# design.net
KiCad netlist of a schematic drawn in Altium Designer
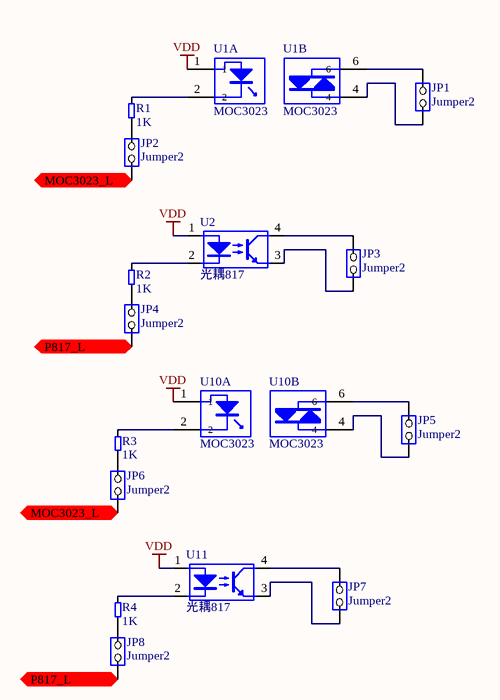
[diagram p0: 光耦隔离.SchDoc]

(export (version "E")
  (design (tool "Eeschema 10.0.6"))
  (components
    (comp (ref "JP1")
      (value "Jumper2")
      (footprint "CON2-P2.54")
      (libsource (lib "Miscellaneous Connectors") (part "Jumper2"))
    )
    (comp (ref "JP2")
      (value "Jumper2")
      (footprint "CON2-P2.54")
      (libsource (lib "Miscellaneous Connectors") (part "Jumper2"))
    )
    (comp (ref "JP3")
      (value "Jumper2")
      (footprint "CON2-P2.54")
      (libsource (lib "Miscellaneous Connectors") (part "Jumper2"))
    )
    (comp (ref "JP4")
      (value "Jumper2")
      (footprint "CON2-P2.54")
      (libsource (lib "Miscellaneous Connectors") (part "Jumper2"))
    )
    (comp (ref "JP5")
      (value "Jumper2")
      (footprint "CON2-P2.54")
      (libsource (lib "Miscellaneous Connectors") (part "Jumper2"))
    )
    (comp (ref "JP6")
      (value "Jumper2")
      (footprint "CON2-P2.54")
      (libsource (lib "Miscellaneous Connectors") (part "Jumper2"))
    )
    (comp (ref "JP7")
      (value "Jumper2")
      (footprint "CON2-P2.54")
      (libsource (lib "Miscellaneous Connectors") (part "Jumper2"))
    )
    (comp (ref "JP8")
      (value "Jumper2")
      (footprint "CON2-P2.54")
      (libsource (lib "Miscellaneous Connectors") (part "Jumper2"))
    )
    (comp (ref "R1")
      (value "1K")
      (footprint "0603")
      (description "电阻")
      (fields (field (name "PUBLISHER") "Altium Limited"))
      (libsource (lib "Miscellaneous Devices") (part "Res1"))
    )
    (comp (ref "R2")
      (value "1K")
      (footprint "0603")
      (description "电阻")
      (fields (field (name "PUBLISHER") "Altium Limited"))
      (libsource (lib "Miscellaneous Devices") (part "Res1"))
    )
    (comp (ref "R3")
      (value "1K")
      (footprint "0603")
      (description "电阻")
      (fields (field (name "PUBLISHER") "Altium Limited"))
      (libsource (lib "Miscellaneous Devices") (part "Res1"))
    )
    (comp (ref "R4")
      (value "1K")
      (footprint "0603")
      (description "电阻")
      (fields (field (name "PUBLISHER") "Altium Limited"))
      (libsource (lib "Miscellaneous Devices") (part "Res1"))
    )
    (comp (ref "U1")
      (value "MOC3023")
      (footprint "SOP-6")
      (description "光耦")
      (fields (field (name "PUBLISHER") "Altium Limited"))
      (libsource (lib "Miscellaneous Devices") (part "MOC3023"))
    )
    (comp (ref "U2")
      (value "光耦817")
      (footprint "LC-SMD-4")
      (libsource (lib "Miscellaneous Devices") (part "光耦817"))
    )
    (comp (ref "U10")
      (value "MOC3023")
      (footprint "SOP-6")
      (description "光耦")
      (fields (field (name "PUBLISHER") "Altium Limited"))
      (libsource (lib "Miscellaneous Devices") (part "MOC3023"))
    )
    (comp (ref "U11")
      (value "光耦817")
      (footprint "LC-SMD-4")
      (libsource (lib "Miscellaneous Devices") (part "光耦817"))
    )
  )
  (nets
    (net (code "1") (name "/MOC3023_L") (class "Default")
      (node (ref "JP2") (pin "1") (pinfunction "COMMON_1") (pintype "passive"))
      (node (ref "JP6") (pin "1") (pinfunction "COMMON_1") (pintype "passive"))
    )
    (net (code "2") (name "/P817_L") (class "Default")
      (node (ref "JP4") (pin "1") (pinfunction "COMMON_1") (pintype "passive"))
      (node (ref "JP8") (pin "1") (pinfunction "COMMON_1") (pintype "passive"))
    )
    (net (code "3") (name "Net-(JP1-COMMON)") (class "Default")
      (node (ref "JP1") (pin "1") (pinfunction "COMMON_1") (pintype "passive"))
      (node (ref "U1") (pin "4") (pinfunction "4_4") (pintype "passive"))
    )
    (net (code "4") (name "Net-(JP1-NO)") (class "Default")
      (node (ref "JP1") (pin "2") (pinfunction "NO_2") (pintype "passive"))
      (node (ref "U1") (pin "6") (pinfunction "6_6") (pintype "passive"))
    )
    (net (code "5") (name "Net-(JP2-NO)") (class "Default")
      (node (ref "JP2") (pin "2") (pinfunction "NO_2") (pintype "passive"))
      (node (ref "R1") (pin "1") (pinfunction "1_1") (pintype "passive"))
    )
    (net (code "6") (name "Net-(JP3-COMMON)") (class "Default")
      (node (ref "JP3") (pin "1") (pinfunction "COMMON_1") (pintype "passive"))
      (node (ref "U2") (pin "3") (pinfunction "Emitter_3") (pintype "passive"))
    )
    (net (code "7") (name "Net-(JP3-NO)") (class "Default")
      (node (ref "JP3") (pin "2") (pinfunction "NO_2") (pintype "passive"))
      (node (ref "U2") (pin "4") (pinfunction "Collector_4") (pintype "passive"))
    )
    (net (code "8") (name "Net-(JP4-NO)") (class "Default")
      (node (ref "JP4") (pin "2") (pinfunction "NO_2") (pintype "passive"))
      (node (ref "R2") (pin "1") (pinfunction "1_1") (pintype "passive"))
    )
    (net (code "9") (name "Net-(JP5-COMMON)") (class "Default")
      (node (ref "JP5") (pin "1") (pinfunction "COMMON_1") (pintype "passive"))
      (node (ref "U10") (pin "4") (pinfunction "4_4") (pintype "passive"))
    )
    (net (code "10") (name "Net-(JP5-NO)") (class "Default")
      (node (ref "JP5") (pin "2") (pinfunction "NO_2") (pintype "passive"))
      (node (ref "U10") (pin "6") (pinfunction "6_6") (pintype "passive"))
    )
    (net (code "11") (name "Net-(JP6-NO)") (class "Default")
      (node (ref "JP6") (pin "2") (pinfunction "NO_2") (pintype "passive"))
      (node (ref "R3") (pin "1") (pinfunction "1_1") (pintype "passive"))
    )
    (net (code "12") (name "Net-(JP7-COMMON)") (class "Default")
      (node (ref "JP7") (pin "1") (pinfunction "COMMON_1") (pintype "passive"))
      (node (ref "U11") (pin "3") (pinfunction "Emitter_3") (pintype "passive"))
    )
    (net (code "13") (name "Net-(JP7-NO)") (class "Default")
      (node (ref "JP7") (pin "2") (pinfunction "NO_2") (pintype "passive"))
      (node (ref "U11") (pin "4") (pinfunction "Collector_4") (pintype "passive"))
    )
    (net (code "14") (name "Net-(JP8-NO)") (class "Default")
      (node (ref "JP8") (pin "2") (pinfunction "NO_2") (pintype "passive"))
      (node (ref "R4") (pin "1") (pinfunction "1_1") (pintype "passive"))
    )
    (net (code "15") (name "Net-(R1-Pad2)") (class "Default")
      (node (ref "R1") (pin "2") (pinfunction "2_2") (pintype "passive"))
      (node (ref "U1") (pin "2") (pinfunction "2_2") (pintype "passive"))
    )
    (net (code "16") (name "Net-(R3-Pad2)") (class "Default")
      (node (ref "R3") (pin "2") (pinfunction "2_2") (pintype "passive"))
      (node (ref "U10") (pin "2") (pinfunction "2_2") (pintype "passive"))
    )
    (net (code "17") (name "Net-(U2-LED_Cathode)") (class "Default")
      (node (ref "R2") (pin "2") (pinfunction "2_2") (pintype "passive"))
      (node (ref "U2") (pin "2") (pinfunction "LED_Cathode_2") (pintype "passive"))
    )
    (net (code "18") (name "Net-(U11-LED_Cathode)") (class "Default")
      (node (ref "R4") (pin "2") (pinfunction "2_2") (pintype "passive"))
      (node (ref "U11") (pin "2") (pinfunction "LED_Cathode_2") (pintype "passive"))
    )
    (net (code "19") (name "VDD") (class "Default")
      (node (ref "U1") (pin "1") (pinfunction "1_1") (pintype "passive"))
      (node (ref "U10") (pin "1") (pinfunction "1_1") (pintype "passive"))
      (node (ref "U11") (pin "1") (pinfunction "LED_Anode_1") (pintype "passive"))
      (node (ref "U2") (pin "1") (pinfunction "LED_Anode_1") (pintype "passive"))
    )
  )
)
